# CLOCKING.net
KiCad netlist of a schematic drawn in Altium Designer
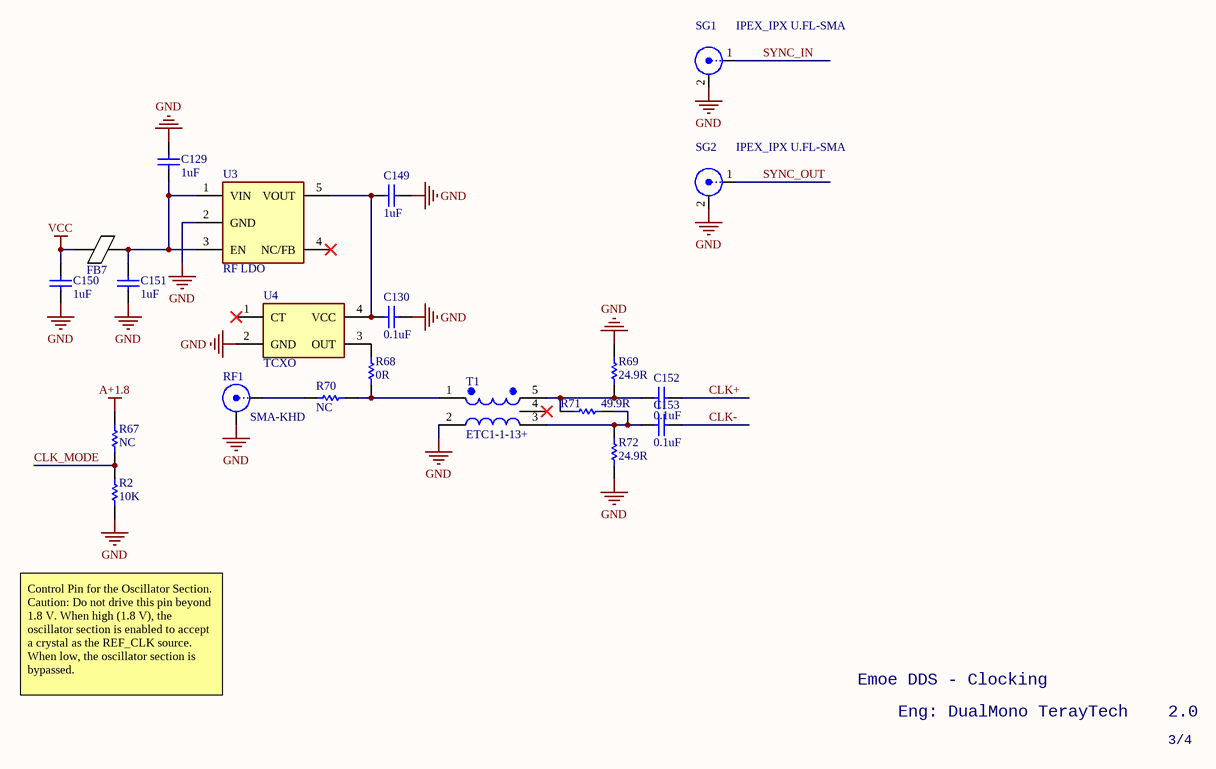
[diagram p0: CLOCKING.SchDoc]

(export (version "E")
  (design (tool "Eeschema 10.0.6"))
  (components
    (comp (ref "C129")
      (value "1uF")
      (footprint "0603_C")
      (description "Capacitor")
      (fields (field (name "PUBLISHER") "Altium Limited"))
      (libsource (lib "My Footprint") (part "CAP"))
    )
    (comp (ref "C130")
      (value "0.1uF")
      (footprint "0402")
      (description "Capacitor")
      (fields (field (name "PUBLISHER") "Altium Limited"))
      (libsource (lib "My Footprint") (part "CAP"))
    )
    (comp (ref "C149")
      (value "1uF")
      (footprint "0603_C")
      (description "Capacitor")
      (fields (field (name "PUBLISHER") "Altium Limited"))
      (libsource (lib "My Footprint") (part "CAP"))
    )
    (comp (ref "C150")
      (value "1uF")
      (footprint "0603_C")
      (description "Capacitor")
      (fields (field (name "PUBLISHER") "Altium Limited"))
      (libsource (lib "My Footprint") (part "CAP"))
    )
    (comp (ref "C151")
      (value "1uF")
      (footprint "0603_C")
      (description "Capacitor")
      (fields (field (name "PUBLISHER") "Altium Limited"))
      (libsource (lib "My Footprint") (part "CAP"))
    )
    (comp (ref "C152")
      (value "0.1uF")
      (footprint "0402l")
      (description "Capacitor")
      (fields (field (name "PUBLISHER") "Altium Limited"))
      (libsource (lib "My Footprint") (part "CAP"))
    )
    (comp (ref "C153")
      (value "0.1uF")
      (footprint "0402l")
      (description "Capacitor")
      (fields (field (name "PUBLISHER") "Altium Limited"))
      (libsource (lib "My Footprint") (part "CAP"))
    )
    (comp (ref "FB7")
      (value "600Ω @ 100MHz")
      (footprint "0603")
      (description "磁珠 600Ω @ 100MHz")
      (libsource (lib "My Footprint") (part "FB"))
    )
    (comp (ref "R2")
      (value "10K")
      (footprint "0402")
      (description "Resistor")
      (fields (field (name "PUBLISHER") "Altium Limited"))
      (libsource (lib "My Footprint") (part "RES"))
    )
    (comp (ref "R67")
      (value "NC")
      (footprint "0402L")
      (description "Resistor")
      (fields (field (name "PUBLISHER") "Altium Limited"))
      (libsource (lib "My Footprint") (part "RES"))
    )
    (comp (ref "R68")
      (value "0R")
      (footprint "0402")
      (description "Resistor")
      (fields (field (name "PUBLISHER") "Altium Limited"))
      (libsource (lib "My Footprint") (part "RES"))
    )
    (comp (ref "R69")
      (value "24.9R")
      (footprint "0402L")
      (description "Resistor")
      (fields (field (name "PUBLISHER") "Altium Limited"))
      (libsource (lib "My Footprint") (part "RES"))
    )
    (comp (ref "R70")
      (value "NC")
      (footprint "0402")
      (description "Resistor")
      (fields (field (name "PUBLISHER") "Altium Limited"))
      (libsource (lib "My Footprint") (part "RES"))
    )
    (comp (ref "R71")
      (value "49.9R")
      (footprint "0402L")
      (description "Resistor")
      (fields (field (name "PUBLISHER") "Altium Limited"))
      (libsource (lib "My Footprint") (part "RES"))
    )
    (comp (ref "R72")
      (value "24.9R")
      (footprint "0402L")
      (description "Resistor")
      (fields (field (name "PUBLISHER") "Altium Limited"))
      (libsource (lib "My Footprint") (part "RES"))
    )
    (comp (ref "RF1") (value "SMA-KHD") (footprint "SMA-5") (libsource (lib "My Footprint") (part "SMA_KHD")))
    (comp (ref "SG1")
      (value "IPEX_IPX U.FL-SMA")
      (footprint "IPEX_gen1")
      (libsource (lib "My Footprint") (part "IPEX_IPX U.FL-SMA"))
    )
    (comp (ref "SG2")
      (value "IPEX_IPX U.FL-SMA")
      (footprint "IPEX_gen1")
      (libsource (lib "My Footprint") (part "IPEX_IPX U.FL-SMA"))
    )
    (comp (ref "T1")
      (value "ETC1-1-13+")
      (footprint "BALUN-5")
      (libsource (lib "SamacSys") (part "ETC1-1-13"))
    )
    (comp (ref "U3") (value "RF LDO") (footprint "SOT-23-5") (libsource (lib "My Footprint") (part "ADP150")))
    (comp (ref "U4") (value "TCXO") (footprint "OSC_KH3225_4P") (libsource (lib "SamacSys") (part "TCXO")))
  )
  (nets
    (net (code "1") (name "/CLK+") (class "Default")
      (node (ref "C152") (pin "2") (pinfunction "2_2") (pintype "passive"))
    )
    (net (code "2") (name "/CLK-") (class "Default")
      (node (ref "C153") (pin "2") (pinfunction "2_2") (pintype "passive"))
    )
    (net (code "3") (name "/CLK_MODE") (class "Default")
      (node (ref "R2") (pin "1") (pinfunction "1_1") (pintype "passive"))
      (node (ref "R67") (pin "2") (pinfunction "2_2") (pintype "passive"))
    )
    (net (code "4") (name "/SYNC_IN") (class "Default")
      (node (ref "SG1") (pin "1") (pinfunction "X_1") (pintype "passive"))
    )
    (net (code "5") (name "/SYNC_OUT") (class "Default")
      (node (ref "SG2") (pin "1") (pinfunction "X_1") (pintype "passive"))
    )
    (net (code "6") (name "A+1.8") (class "Default")
      (node (ref "R67") (pin "1") (pinfunction "1_1") (pintype "passive"))
    )
    (net (code "7") (name "GND") (class "Default")
      (node (ref "C129") (pin "1") (pinfunction "1_1") (pintype "passive"))
      (node (ref "C130") (pin "2") (pinfunction "2_2") (pintype "passive"))
      (node (ref "C149") (pin "1") (pinfunction "1_1") (pintype "passive"))
      (node (ref "C150") (pin "1") (pinfunction "1_1") (pintype "passive"))
      (node (ref "C151") (pin "1") (pinfunction "1_1") (pintype "passive"))
      (node (ref "R2") (pin "2") (pinfunction "2_2") (pintype "passive"))
      (node (ref "R69") (pin "1") (pinfunction "1_1") (pintype "passive"))
      (node (ref "R72") (pin "1") (pinfunction "1_1") (pintype "passive"))
      (node (ref "RF1") (pin "1") (pinfunction "2_1") (pintype "passive"))
      (node (ref "SG1") (pin "2") (pinfunction "GND_2") (pintype "passive"))
      (node (ref "SG2") (pin "2") (pinfunction "GND_2") (pintype "passive"))
      (node (ref "T1") (pin "2") (pinfunction "2_2") (pintype "passive"))
      (node (ref "U3") (pin "2") (pinfunction "GND_2") (pintype "passive"))
      (node (ref "U4") (pin "2") (pinfunction "GND_2") (pintype "passive"))
    )
    (net (code "8") (name "Net-(C152-Pad1)") (class "Default")
      (node (ref "C152") (pin "1") (pinfunction "1_1") (pintype "passive"))
      (node (ref "R69") (pin "2") (pinfunction "2_2") (pintype "passive"))
      (node (ref "R71") (pin "1") (pinfunction "1_1") (pintype "passive"))
      (node (ref "T1") (pin "5") (pinfunction "5_5") (pintype "passive"))
    )
    (net (code "9") (name "Net-(C153-Pad1)") (class "Default")
      (node (ref "C153") (pin "1") (pinfunction "1_1") (pintype "passive"))
      (node (ref "R71") (pin "2") (pinfunction "2_2") (pintype "passive"))
      (node (ref "R72") (pin "2") (pinfunction "2_2") (pintype "passive"))
      (node (ref "T1") (pin "3") (pinfunction "3_3") (pintype "passive"))
    )
    (net (code "10") (name "Net-(R68-Pad2)") (class "Default")
      (node (ref "R68") (pin "2") (pinfunction "2_2") (pintype "passive"))
      (node (ref "R70") (pin "2") (pinfunction "2_2") (pintype "passive"))
      (node (ref "T1") (pin "1") (pinfunction "1_1") (pintype "passive"))
    )
    (net (code "11") (name "Net-(RF1-1)") (class "Default")
      (node (ref "R70") (pin "1") (pinfunction "1_1") (pintype "passive"))
      (node (ref "RF1") (pin "2") (pinfunction "1_2") (pintype "passive"))
    )
    (net (code "12") (name "Net-(U3-EN)") (class "Default")
      (node (ref "C129") (pin "2") (pinfunction "2_2") (pintype "passive"))
      (node (ref "C151") (pin "2") (pinfunction "2_2") (pintype "passive"))
      (node (ref "FB7") (pin "2") (pinfunction "2_2") (pintype "passive"))
      (node (ref "U3") (pin "1") (pinfunction "VIN_1") (pintype "passive"))
      (node (ref "U3") (pin "3") (pinfunction "EN_3") (pintype "passive"))
    )
    (net (code "13") (name "Net-(U3-VOUT)") (class "Default")
      (node (ref "C130") (pin "1") (pinfunction "1_1") (pintype "passive"))
      (node (ref "C149") (pin "2") (pinfunction "2_2") (pintype "passive"))
      (node (ref "U3") (pin "5") (pinfunction "VOUT_5") (pintype "passive"))
      (node (ref "U4") (pin "4") (pinfunction "VCC_4") (pintype "passive"))
    )
    (net (code "14") (name "Net-(U4-OUT)") (class "Default")
      (node (ref "R68") (pin "1") (pinfunction "1_1") (pintype "passive"))
      (node (ref "U4") (pin "3") (pinfunction "OUT_3") (pintype "passive"))
    )
    (net (code "15") (name "VCC") (class "Default")
      (node (ref "C150") (pin "2") (pinfunction "2_2") (pintype "passive"))
      (node (ref "FB7") (pin "1") (pinfunction "1_1") (pintype "passive"))
    )
    (net (code "16") (name "unconnected-(T1-Pad4)") (class "Default")
      (node (ref "T1") (pin "4") (pinfunction "4_4") (pintype "passive+no_connect"))
    )
    (net (code "17") (name "unconnected-(U3-NC{slash}FB-Pad4)") (class "Default")
      (node (ref "U3") (pin "4") (pinfunction "NC/FB_4") (pintype "passive+no_connect"))
    )
    (net (code "18") (name "unconnected-(U4-CT-Pad1)") (class "Default")
      (node (ref "U4") (pin "1") (pinfunction "CT_1") (pintype "passive+no_connect"))
    )
  )
)
